# eeZeeProp.net
KiCad netlist of a schematic drawn in EAGLE
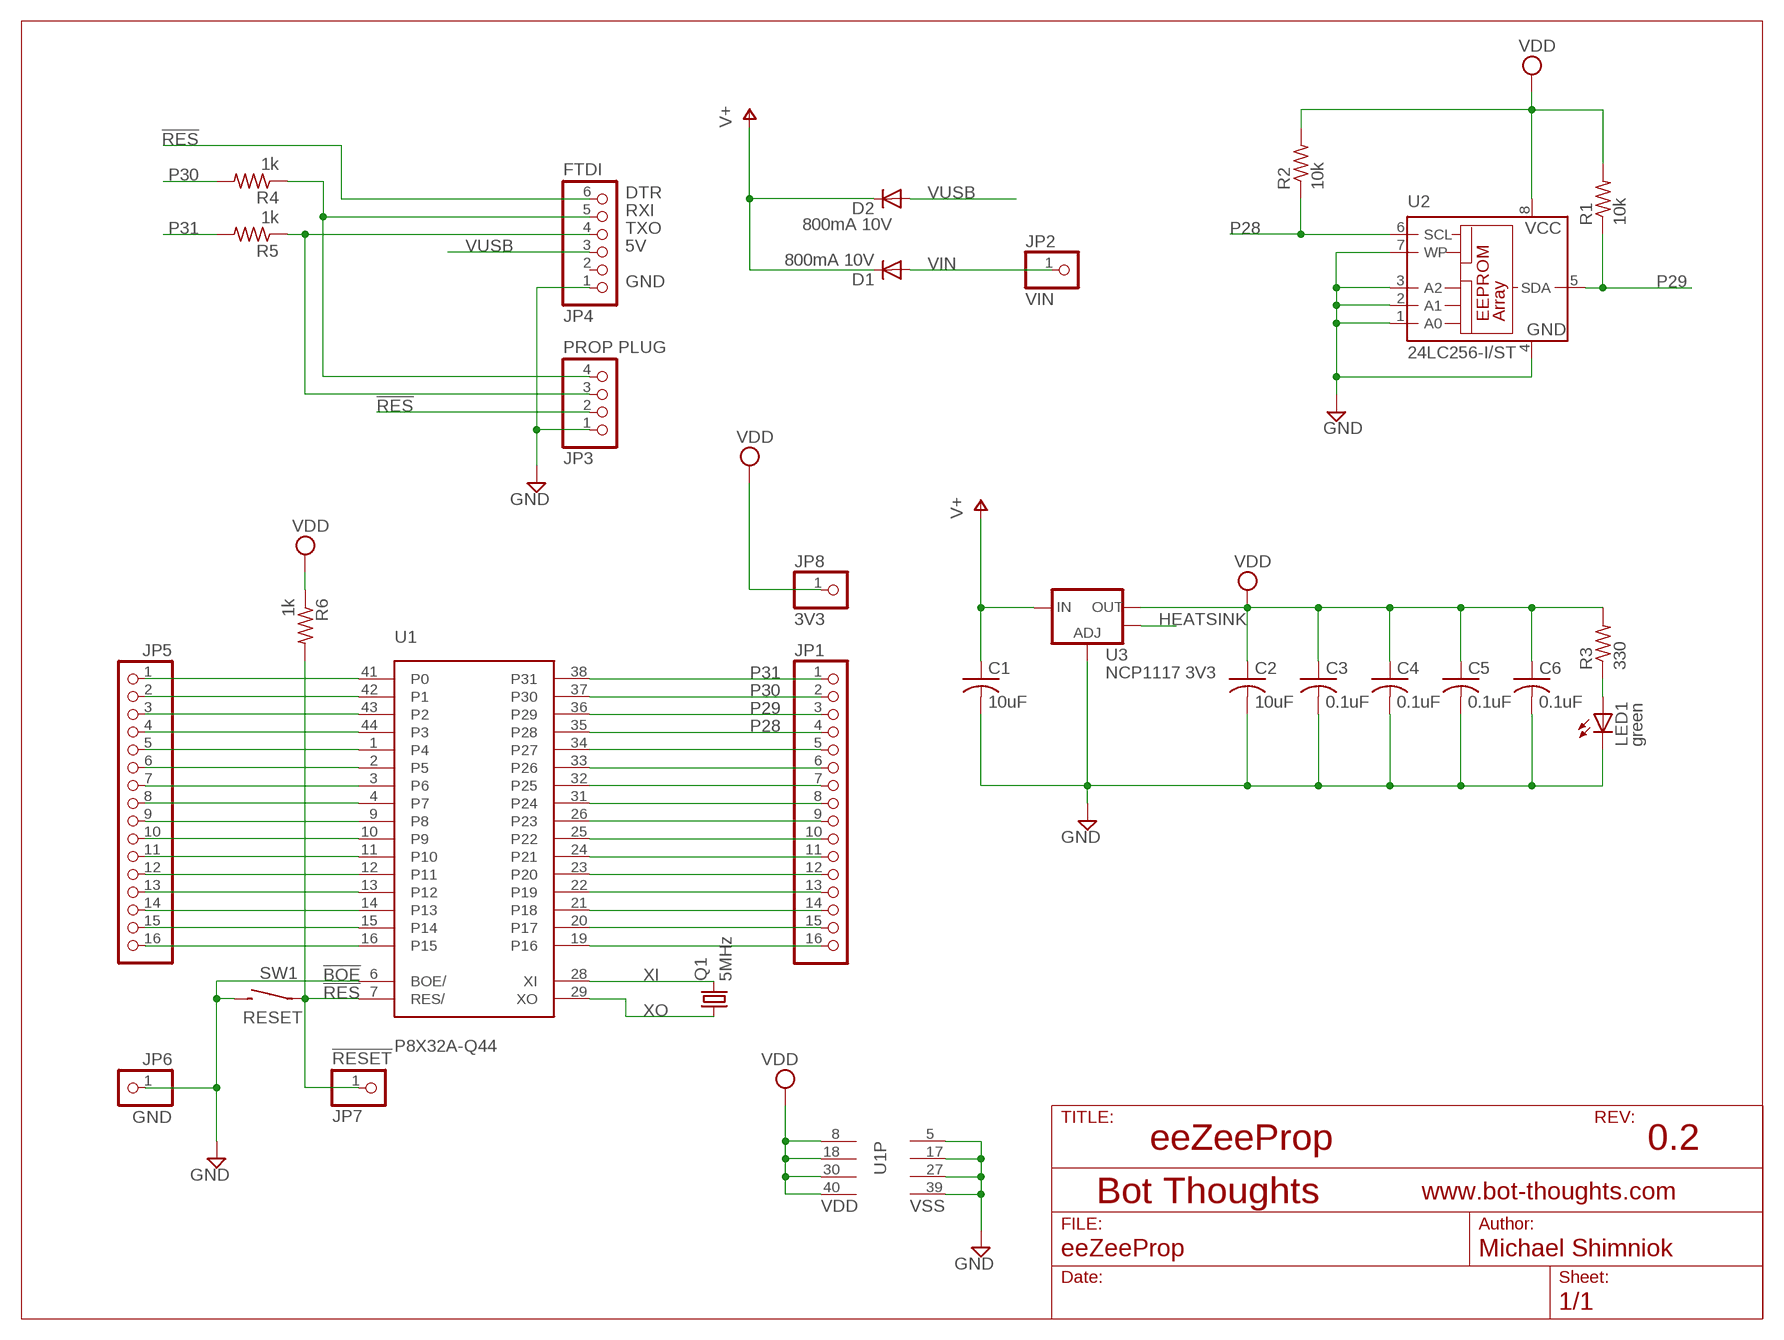
[diagram p0: schematic, sheet 1]

(export (version "E")
  (design (tool "Eeschema 10.0.6"))
  (components
    (comp (ref "C1")
      (value "10uF")
      (footprint "eagle-import:C1206")
      (fields (field (name "PARTNO") "T491A106M006AT"))
      (libsource (lib "eagle-import") (part "C-USC1206"))
    )
    (comp (ref "C2")
      (value "10uF")
      (footprint "eagle-import:C1206")
      (fields (field (name "PARTNO") "T491A106M006AT"))
      (libsource (lib "eagle-import") (part "C-USC1206"))
    )
    (comp (ref "C3")
      (value "0.1uF")
      (footprint "eagle-import:C0603")
      (fields (field (name "PARTNO") "0603YC104KAT2A"))
      (libsource (lib "eagle-import") (part "C-USC0603"))
    )
    (comp (ref "C4")
      (value "0.1uF")
      (footprint "eagle-import:C0603")
      (fields (field (name "PARTNO") "0603YC104KAT2A"))
      (libsource (lib "eagle-import") (part "C-USC0603"))
    )
    (comp (ref "C5")
      (value "0.1uF")
      (footprint "eagle-import:C0603")
      (fields (field (name "PARTNO") "0603YC104KAT2A"))
      (libsource (lib "eagle-import") (part "C-USC0603"))
    )
    (comp (ref "C6")
      (value "0.1uF")
      (footprint "eagle-import:C0603")
      (fields (field (name "PARTNO") "0603YC104KAT2A"))
      (libsource (lib "eagle-import") (part "C-USC0603"))
    )
    (comp (ref "D1")
      (value "800mA 10V")
      (footprint "eagle-import:SOD323-R")
      (fields (field (name "PARTNO") "PMEG2015EA,115"))
      (libsource (lib "eagle-import") (part "DIODE-SOD323-R"))
    )
    (comp (ref "D2")
      (value "800mA 10V")
      (footprint "eagle-import:SOD323-R")
      (fields (field (name "PARTNO") "PMEG2015EA,115"))
      (libsource (lib "eagle-import") (part "DIODE-SOD323-R"))
    )
    (comp (ref "JP1")
      (value "PINHD-1X16_2.54-S")
      (footprint "eagle-import:1X16-S")
      (libsource (lib "eagle-import") (part "PINHD-1X16_2.54-S"))
    )
    (comp (ref "JP2")
      (value "VIN")
      (footprint "eagle-import:1X01")
      (libsource (lib "eagle-import") (part "PINHD-1X01_2.54"))
    )
    (comp (ref "JP3")
      (value "PROP PLUG")
      (footprint "eagle-import:1X04_90-S")
      (libsource (lib "eagle-import") (part "PINHD-1X04_2.54-90°-S"))
    )
    (comp (ref "JP4")
      (value "FTDI")
      (footprint "eagle-import:1X06-S")
      (fields (field (name "PARTNO") "2211S-06G"))
      (libsource (lib "eagle-import") (part "PINHD-1X06_2.54-S"))
    )
    (comp (ref "JP5")
      (value "PINHD-1X16_2.54-S")
      (footprint "eagle-import:1X16-S")
      (libsource (lib "eagle-import") (part "PINHD-1X16_2.54-S"))
    )
    (comp (ref "JP6")
      (value "GND")
      (footprint "eagle-import:1X01")
      (libsource (lib "eagle-import") (part "PINHD-1X01_2.54"))
    )
    (comp (ref "JP7")
      (value "!RESET")
      (footprint "eagle-import:1X01")
      (libsource (lib "eagle-import") (part "PINHD-1X01_2.54"))
    )
    (comp (ref "JP8")
      (value "3V3")
      (footprint "eagle-import:1X01")
      (libsource (lib "eagle-import") (part "PINHD-1X01_2.54"))
    )
    (comp (ref "LED1")
      (value "green")
      (footprint "eagle-import:CHIPLED_1206")
      (fields (field (name "PARTNO") "LG N971-KN-1"))
      (libsource (lib "eagle-import") (part "LEDCHIPLED_1206"))
    )
    (comp (ref "Q1")
      (value "5MHz")
      (footprint "eagle-import:HC49U-V")
      (fields (field (name "OC_FARNELL") "1666969") (field (name "PARTNO") "HC49US-5.000MABJ-UB"))
      (libsource (lib "eagle-import") (part "CRYSTALHC49U-V"))
    )
    (comp (ref "R1")
      (value "10k")
      (footprint "eagle-import:R0603")
      (fields (field (name "PARTNO") "ERJ-3GEYJ103V"))
      (libsource (lib "eagle-import") (part "R-US_R0603"))
    )
    (comp (ref "R2")
      (value "10k")
      (footprint "eagle-import:R0603")
      (fields (field (name "PARTNO") "ERJ-3GEYJ103V"))
      (libsource (lib "eagle-import") (part "R-US_R0603"))
    )
    (comp (ref "R3")
      (value "330")
      (footprint "eagle-import:R0603")
      (fields (field (name "PARTNO") "ERJ-3GEYJ331V"))
      (libsource (lib "eagle-import") (part "R-US_R0603"))
    )
    (comp (ref "R4")
      (value "1k")
      (footprint "eagle-import:R0603")
      (fields (field (name "PARTNO") "RC0603JR-071KL"))
      (libsource (lib "eagle-import") (part "R-US_R0603"))
    )
    (comp (ref "R5")
      (value "1k")
      (footprint "eagle-import:R0603")
      (fields (field (name "PARTNO") "RC0603JR-071KL"))
      (libsource (lib "eagle-import") (part "R-US_R0603"))
    )
    (comp (ref "R6")
      (value "1k")
      (footprint "eagle-import:R0603")
      (fields (field (name "PARTNO") "RC0603JR-071KL"))
      (libsource (lib "eagle-import") (part "R-US_R0603"))
    )
    (comp (ref "SW1")
      (value "RESET")
      (footprint "eagle-import:6MMTACTILE_RECT")
      (fields (field (name "PARTNO") "MJTP1243"))
      (libsource (lib "eagle-import") (part "SPST_TAC_RECT1"))
    )
    (comp (ref "U1")
      (value "P8X32A-Q44")
      (footprint "eagle-import:P8X32A-Q44")
      (fields (field (name "PARTNO") "P8X32A-Q44"))
      (libsource (lib "eagle-import") (part "P8X32A-Q44"))
    )
    (comp (ref "U2")
      (value "24LC256-I/ST")
      (footprint "eagle-import:SO-08")
      (fields
        (field (name "MF") "MICROCHIP")
        (field (name "MPN") "24LC128-I/SNG")
        (field (name "MF_1") "OnSemi")
        (field (name "MPN_1") "CAT24C256WI-GT3")
        (field (name "PARTNO") "CAT24C256WI-GT3")
      )
      (libsource (lib "eagle-import") (part "24SNLC128"))
    )
    (comp (ref "U3")
      (value "NCP1117 3V3")
      (footprint "eagle-import:SOT223")
      (fields (field (name "PARTNO") "SPX1117M3-L-3-3"))
      (libsource (lib "eagle-import") (part "V_REG_LM1117SOT223"))
    )
  )
  (nets
    (net (code "1") (name "/HEATSINK") (class "Default")
      (node (ref "U3") (pin "4") (pinfunction "OUT_4") (pintype "output"))
    )
    (net (code "2") (name "/P28") (class "Default")
      (node (ref "JP1") (pin "4") (pinfunction "4_4") (pintype "passive"))
      (node (ref "R2") (pin "1") (pinfunction "1_1") (pintype "passive"))
      (node (ref "U1") (pin "35") (pinfunction "P28_35") (pintype "bidirectional"))
      (node (ref "U2") (pin "6") (pinfunction "SCL_6") (pintype "input"))
    )
    (net (code "3") (name "/P29") (class "Default")
      (node (ref "JP1") (pin "3") (pinfunction "3_3") (pintype "passive"))
      (node (ref "R1") (pin "1") (pinfunction "1_1") (pintype "passive"))
      (node (ref "U1") (pin "36") (pinfunction "P29_36") (pintype "bidirectional"))
      (node (ref "U2") (pin "5") (pinfunction "SDA_5") (pintype "bidirectional"))
    )
    (net (code "4") (name "/P30") (class "Default")
      (node (ref "JP1") (pin "2") (pinfunction "2_2") (pintype "passive"))
      (node (ref "R4") (pin "2") (pinfunction "2_2") (pintype "passive"))
      (node (ref "U1") (pin "37") (pinfunction "P30_37") (pintype "bidirectional"))
    )
    (net (code "5") (name "/P31") (class "Default")
      (node (ref "JP1") (pin "1") (pinfunction "1_1") (pintype "passive"))
      (node (ref "R5") (pin "2") (pinfunction "2_2") (pintype "passive"))
      (node (ref "U1") (pin "38") (pinfunction "P31_38") (pintype "bidirectional"))
    )
    (net (code "6") (name "/VIN") (class "Default")
      (node (ref "D1") (pin "A") (pinfunction "A_A") (pintype "passive"))
      (node (ref "JP2") (pin "1") (pinfunction "1_1") (pintype "passive"))
    )
    (net (code "7") (name "/VUSB") (class "Default")
      (node (ref "D2") (pin "A") (pinfunction "A_A") (pintype "passive"))
      (node (ref "JP4") (pin "3") (pinfunction "3_3") (pintype "passive"))
    )
    (net (code "8") (name "/XI") (class "Default")
      (node (ref "Q1") (pin "2") (pinfunction "2_2") (pintype "passive"))
      (node (ref "U1") (pin "28") (pinfunction "XI_28") (pintype "input"))
    )
    (net (code "9") (name "/XO") (class "Default")
      (node (ref "Q1") (pin "1") (pinfunction "1_1") (pintype "passive"))
      (node (ref "U1") (pin "29") (pinfunction "XO_29") (pintype "output"))
    )
    (net (code "10") (name "/~{RES}") (class "Default")
      (node (ref "JP3") (pin "2") (pinfunction "2_2") (pintype "passive"))
      (node (ref "JP4") (pin "6") (pinfunction "6_6") (pintype "passive"))
      (node (ref "JP7") (pin "1") (pinfunction "1_1") (pintype "passive"))
      (node (ref "R6") (pin "2") (pinfunction "2_2") (pintype "passive"))
      (node (ref "SW1") (pin "P$1") (pinfunction "P_P$1") (pintype "passive"))
      (node (ref "U1") (pin "7") (pinfunction "RES/_7") (pintype "bidirectional"))
    )
    (net (code "11") (name "GND") (class "Default")
      (node (ref "C1") (pin "2") (pinfunction "2_2") (pintype "passive"))
      (node (ref "C2") (pin "2") (pinfunction "2_2") (pintype "passive"))
      (node (ref "C3") (pin "2") (pinfunction "2_2") (pintype "passive"))
      (node (ref "C4") (pin "2") (pinfunction "2_2") (pintype "passive"))
      (node (ref "C5") (pin "2") (pinfunction "2_2") (pintype "passive"))
      (node (ref "C6") (pin "2") (pinfunction "2_2") (pintype "passive"))
      (node (ref "JP3") (pin "1") (pinfunction "1_1") (pintype "passive"))
      (node (ref "JP4") (pin "1") (pinfunction "1_1") (pintype "passive"))
      (node (ref "JP6") (pin "1") (pinfunction "1_1") (pintype "passive"))
      (node (ref "LED1") (pin "C") (pinfunction "C_C") (pintype "passive"))
      (node (ref "SW1") (pin "P$2") (pinfunction "S_P$2") (pintype "passive"))
      (node (ref "U1") (pin "17") (pinfunction "VSS_17") (pintype "power_in"))
      (node (ref "U1") (pin "27") (pinfunction "VSS_27") (pintype "power_in"))
      (node (ref "U1") (pin "39") (pinfunction "VSS_39") (pintype "power_in"))
      (node (ref "U1") (pin "5") (pinfunction "VSS_5") (pintype "power_in"))
      (node (ref "U1") (pin "6") (pinfunction "BOE/_6") (pintype "input"))
      (node (ref "U2") (pin "1") (pinfunction "A0_1") (pintype "input"))
      (node (ref "U2") (pin "2") (pinfunction "A1_2") (pintype "input"))
      (node (ref "U2") (pin "3") (pinfunction "A2_3") (pintype "input"))
      (node (ref "U2") (pin "4") (pinfunction "GND_4") (pintype "power_in"))
      (node (ref "U2") (pin "7") (pinfunction "WP_7") (pintype "input"))
      (node (ref "U3") (pin "1") (pinfunction "ADJ_1") (pintype "input"))
    )
    (net (code "12") (name "Net-(JP3-Pad3)") (class "Default")
      (node (ref "JP3") (pin "3") (pinfunction "3_3") (pintype "passive"))
      (node (ref "JP4") (pin "4") (pinfunction "4_4") (pintype "passive"))
      (node (ref "R5") (pin "1") (pinfunction "1_1") (pintype "passive"))
    )
    (net (code "13") (name "Net-(JP3-Pad4)") (class "Default")
      (node (ref "JP3") (pin "4") (pinfunction "4_4") (pintype "passive"))
      (node (ref "JP4") (pin "5") (pinfunction "5_5") (pintype "passive"))
      (node (ref "R4") (pin "1") (pinfunction "1_1") (pintype "passive"))
    )
    (net (code "14") (name "Net-(LED1-PadA)") (class "Default")
      (node (ref "LED1") (pin "A") (pinfunction "A_A") (pintype "passive"))
      (node (ref "R3") (pin "1") (pinfunction "1_1") (pintype "passive"))
    )
    (net (code "15") (name "Net-(U1B-P0)") (class "Default")
      (node (ref "JP5") (pin "1") (pinfunction "1_1") (pintype "passive"))
      (node (ref "U1") (pin "41") (pinfunction "P0_41") (pintype "bidirectional"))
    )
    (net (code "16") (name "Net-(U1B-P1)") (class "Default")
      (node (ref "JP5") (pin "2") (pinfunction "2_2") (pintype "passive"))
      (node (ref "U1") (pin "42") (pinfunction "P1_42") (pintype "bidirectional"))
    )
    (net (code "17") (name "Net-(U1B-P2)") (class "Default")
      (node (ref "JP5") (pin "3") (pinfunction "3_3") (pintype "passive"))
      (node (ref "U1") (pin "43") (pinfunction "P2_43") (pintype "bidirectional"))
    )
    (net (code "18") (name "Net-(U1B-P3)") (class "Default")
      (node (ref "JP5") (pin "4") (pinfunction "4_4") (pintype "passive"))
      (node (ref "U1") (pin "44") (pinfunction "P3_44") (pintype "bidirectional"))
    )
    (net (code "19") (name "Net-(U1B-P4)") (class "Default")
      (node (ref "JP5") (pin "5") (pinfunction "5_5") (pintype "passive"))
      (node (ref "U1") (pin "1") (pinfunction "P4_1") (pintype "bidirectional"))
    )
    (net (code "20") (name "Net-(U1B-P5)") (class "Default")
      (node (ref "JP5") (pin "6") (pinfunction "6_6") (pintype "passive"))
      (node (ref "U1") (pin "2") (pinfunction "P5_2") (pintype "bidirectional"))
    )
    (net (code "21") (name "Net-(U1B-P6)") (class "Default")
      (node (ref "JP5") (pin "7") (pinfunction "7_7") (pintype "passive"))
      (node (ref "U1") (pin "3") (pinfunction "P6_3") (pintype "bidirectional"))
    )
    (net (code "22") (name "Net-(U1B-P7)") (class "Default")
      (node (ref "JP5") (pin "8") (pinfunction "8_8") (pintype "passive"))
      (node (ref "U1") (pin "4") (pinfunction "P7_4") (pintype "bidirectional"))
    )
    (net (code "23") (name "Net-(U1B-P8)") (class "Default")
      (node (ref "JP5") (pin "9") (pinfunction "9_9") (pintype "passive"))
      (node (ref "U1") (pin "9") (pinfunction "P8_9") (pintype "bidirectional"))
    )
    (net (code "24") (name "Net-(U1B-P9)") (class "Default")
      (node (ref "JP5") (pin "10") (pinfunction "10_10") (pintype "passive"))
      (node (ref "U1") (pin "10") (pinfunction "P9_10") (pintype "bidirectional"))
    )
    (net (code "25") (name "Net-(U1B-P10)") (class "Default")
      (node (ref "JP5") (pin "11") (pinfunction "11_11") (pintype "passive"))
      (node (ref "U1") (pin "11") (pinfunction "P10_11") (pintype "bidirectional"))
    )
    (net (code "26") (name "Net-(U1B-P11)") (class "Default")
      (node (ref "JP5") (pin "12") (pinfunction "12_12") (pintype "passive"))
      (node (ref "U1") (pin "12") (pinfunction "P11_12") (pintype "bidirectional"))
    )
    (net (code "27") (name "Net-(U1B-P12)") (class "Default")
      (node (ref "JP5") (pin "13") (pinfunction "13_13") (pintype "passive"))
      (node (ref "U1") (pin "13") (pinfunction "P12_13") (pintype "bidirectional"))
    )
    (net (code "28") (name "Net-(U1B-P13)") (class "Default")
      (node (ref "JP5") (pin "14") (pinfunction "14_14") (pintype "passive"))
      (node (ref "U1") (pin "14") (pinfunction "P13_14") (pintype "bidirectional"))
    )
    (net (code "29") (name "Net-(U1B-P14)") (class "Default")
      (node (ref "JP5") (pin "15") (pinfunction "15_15") (pintype "passive"))
      (node (ref "U1") (pin "15") (pinfunction "P14_15") (pintype "bidirectional"))
    )
    (net (code "30") (name "Net-(U1B-P15)") (class "Default")
      (node (ref "JP5") (pin "16") (pinfunction "16_16") (pintype "passive"))
      (node (ref "U1") (pin "16") (pinfunction "P15_16") (pintype "bidirectional"))
    )
    (net (code "31") (name "Net-(U1B-P16)") (class "Default")
      (node (ref "JP1") (pin "16") (pinfunction "16_16") (pintype "passive"))
      (node (ref "U1") (pin "19") (pinfunction "P16_19") (pintype "bidirectional"))
    )
    (net (code "32") (name "Net-(U1B-P17)") (class "Default")
      (node (ref "JP1") (pin "15") (pinfunction "15_15") (pintype "passive"))
      (node (ref "U1") (pin "20") (pinfunction "P17_20") (pintype "bidirectional"))
    )
    (net (code "33") (name "Net-(U1B-P18)") (class "Default")
      (node (ref "JP1") (pin "14") (pinfunction "14_14") (pintype "passive"))
      (node (ref "U1") (pin "21") (pinfunction "P18_21") (pintype "bidirectional"))
    )
    (net (code "34") (name "Net-(U1B-P19)") (class "Default")
      (node (ref "JP1") (pin "13") (pinfunction "13_13") (pintype "passive"))
      (node (ref "U1") (pin "22") (pinfunction "P19_22") (pintype "bidirectional"))
    )
    (net (code "35") (name "Net-(U1B-P20)") (class "Default")
      (node (ref "JP1") (pin "12") (pinfunction "12_12") (pintype "passive"))
      (node (ref "U1") (pin "23") (pinfunction "P20_23") (pintype "bidirectional"))
    )
    (net (code "36") (name "Net-(U1B-P21)") (class "Default")
      (node (ref "JP1") (pin "11") (pinfunction "11_11") (pintype "passive"))
      (node (ref "U1") (pin "24") (pinfunction "P21_24") (pintype "bidirectional"))
    )
    (net (code "37") (name "Net-(U1B-P22)") (class "Default")
      (node (ref "JP1") (pin "10") (pinfunction "10_10") (pintype "passive"))
      (node (ref "U1") (pin "25") (pinfunction "P22_25") (pintype "bidirectional"))
    )
    (net (code "38") (name "Net-(U1B-P23)") (class "Default")
      (node (ref "JP1") (pin "9") (pinfunction "9_9") (pintype "passive"))
      (node (ref "U1") (pin "26") (pinfunction "P23_26") (pintype "bidirectional"))
    )
    (net (code "39") (name "Net-(U1B-P24)") (class "Default")
      (node (ref "JP1") (pin "8") (pinfunction "8_8") (pintype "passive"))
      (node (ref "U1") (pin "31") (pinfunction "P24_31") (pintype "bidirectional"))
    )
    (net (code "40") (name "Net-(U1B-P25)") (class "Default")
      (node (ref "JP1") (pin "7") (pinfunction "7_7") (pintype "passive"))
      (node (ref "U1") (pin "32") (pinfunction "P25_32") (pintype "bidirectional"))
    )
    (net (code "41") (name "Net-(U1B-P26)") (class "Default")
      (node (ref "JP1") (pin "6") (pinfunction "6_6") (pintype "passive"))
      (node (ref "U1") (pin "33") (pinfunction "P26_33") (pintype "bidirectional"))
    )
    (net (code "42") (name "Net-(U1B-P27)") (class "Default")
      (node (ref "JP1") (pin "5") (pinfunction "5_5") (pintype "passive"))
      (node (ref "U1") (pin "34") (pinfunction "P27_34") (pintype "bidirectional"))
    )
    (net (code "43") (name "V+") (class "Default")
      (node (ref "C1") (pin "1") (pinfunction "1_1") (pintype "passive"))
      (node (ref "D1") (pin "C") (pinfunction "C_C") (pintype "passive"))
      (node (ref "D2") (pin "C") (pinfunction "C_C") (pintype "passive"))
      (node (ref "U3") (pin "3") (pinfunction "IN_3") (pintype "input"))
    )
    (net (code "44") (name "VDD") (class "Default")
      (node (ref "C2") (pin "1") (pinfunction "1_1") (pintype "passive"))
      (node (ref "C3") (pin "1") (pinfunction "1_1") (pintype "passive"))
      (node (ref "C4") (pin "1") (pinfunction "1_1") (pintype "passive"))
      (node (ref "C5") (pin "1") (pinfunction "1_1") (pintype "passive"))
      (node (ref "C6") (pin "1") (pinfunction "1_1") (pintype "passive"))
      (node (ref "JP8") (pin "1") (pinfunction "1_1") (pintype "passive"))
      (node (ref "R1") (pin "2") (pinfunction "2_2") (pintype "passive"))
      (node (ref "R2") (pin "2") (pinfunction "2_2") (pintype "passive"))
      (node (ref "R3") (pin "2") (pinfunction "2_2") (pintype "passive"))
      (node (ref "R6") (pin "1") (pinfunction "1_1") (pintype "passive"))
      (node (ref "U1") (pin "18") (pinfunction "VDD_18") (pintype "power_in"))
      (node (ref "U1") (pin "30") (pinfunction "VDD_30") (pintype "power_in"))
      (node (ref "U1") (pin "40") (pinfunction "VDD_40") (pintype "power_in"))
      (node (ref "U1") (pin "8") (pinfunction "VDD_8") (pintype "power_in"))
      (node (ref "U2") (pin "8") (pinfunction "VCC_8") (pintype "power_in"))
      (node (ref "U3") (pin "2") (pinfunction "OUT_2") (pintype "output"))
    )
    (net (code "45") (name "unconnected-(JP4-Pad2)") (class "Default")
      (node (ref "JP4") (pin "2") (pinfunction "2_2") (pintype "passive"))
    )
  )
)
